# 02_4G.net
KiCad netlist of a schematic drawn in Altium Designer
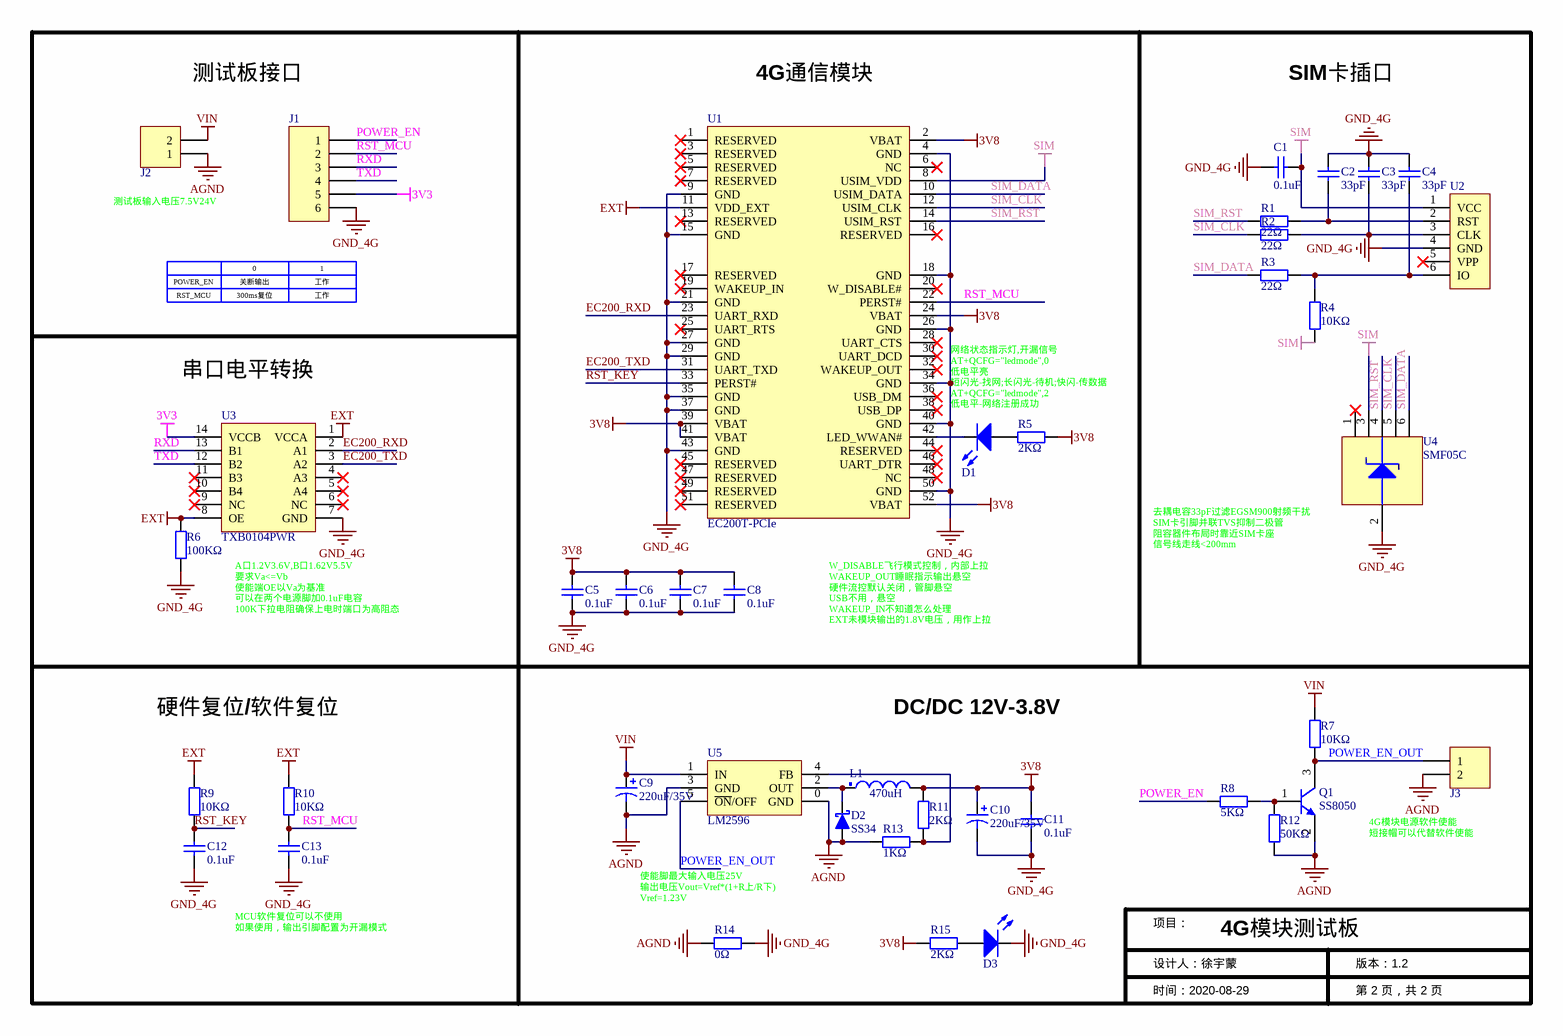
[diagram p0: 02_4G模块测试板原理图.SchDoc]

(export (version "E")
  (design (tool "Eeschema 10.0.6"))
  (components
    (comp (ref "C1")
      (value "0.1uF")
      (footprint "CAP-0603")
      (description "无极性电容")
      (fields (field (name "Comment") "Cap") (field (name "PUBLISHER") "Altium Limited"))
      (libsource (lib "Arrowy_Racing") (part "Cap"))
    )
    (comp (ref "C2")
      (value "33pF")
      (footprint "CAP-0603")
      (description "无极性电容")
      (fields (field (name "Comment") "Cap") (field (name "PUBLISHER") "Altium Limited"))
      (libsource (lib "Arrowy_Racing") (part "Cap"))
    )
    (comp (ref "C3")
      (value "33pF")
      (footprint "CAP-0603")
      (description "无极性电容")
      (fields (field (name "Comment") "Cap") (field (name "PUBLISHER") "Altium Limited"))
      (libsource (lib "Arrowy_Racing") (part "Cap"))
    )
    (comp (ref "C4")
      (value "33pF")
      (footprint "CAP-0603")
      (description "无极性电容")
      (fields (field (name "Comment") "Cap") (field (name "PUBLISHER") "Altium Limited"))
      (libsource (lib "Arrowy_Racing") (part "Cap"))
    )
    (comp (ref "C5")
      (value "0.1uF")
      (footprint "CAP-0603")
      (description "无极性电容")
      (fields (field (name "Comment") "Cap") (field (name "PUBLISHER") "Altium Limited"))
      (libsource (lib "Arrowy_Racing") (part "Cap"))
    )
    (comp (ref "C6")
      (value "0.1uF")
      (footprint "CAP-0603")
      (description "无极性电容")
      (fields (field (name "Comment") "Cap") (field (name "PUBLISHER") "Altium Limited"))
      (libsource (lib "Arrowy_Racing") (part "Cap"))
    )
    (comp (ref "C7")
      (value "0.1uF")
      (footprint "CAP-0603")
      (description "无极性电容")
      (fields (field (name "Comment") "Cap") (field (name "PUBLISHER") "Altium Limited"))
      (libsource (lib "Arrowy_Racing") (part "Cap"))
    )
    (comp (ref "C8")
      (value "0.1uF")
      (footprint "CAP-0603")
      (description "无极性电容")
      (fields (field (name "Comment") "Cap") (field (name "PUBLISHER") "Altium Limited"))
      (libsource (lib "Arrowy_Racing") (part "Cap"))
    )
    (comp (ref "C9")
      (value "220uF/35V")
      (footprint "Cap8x10.5mm")
      (description "贴片电解电容 8*10.5mm")
      (fields (field (name "Comment") "Cap Pol") (field (name "PUBLISHER") "Altium Limited"))
      (libsource (lib "元件库") (part "Cap Pol"))
    )
    (comp (ref "C10")
      (value "220uF/35V")
      (footprint "Cap8x10.5mm")
      (description "贴片电解电容 8*10.5mm")
      (fields (field (name "Comment") "Cap Pol") (field (name "PUBLISHER") "Altium Limited"))
      (libsource (lib "元件库") (part "Cap Pol"))
    )
    (comp (ref "C11")
      (value "0.1uF")
      (footprint "CAP-0603")
      (description "无极性电容")
      (fields (field (name "Comment") "Cap") (field (name "PUBLISHER") "Altium Limited"))
      (libsource (lib "Arrowy_Racing") (part "Cap"))
    )
    (comp (ref "C12")
      (value "0.1uF")
      (footprint "CAP-0603")
      (description "无极性电容")
      (fields (field (name "Comment") "Cap") (field (name "PUBLISHER") "Altium Limited"))
      (libsource (lib "Arrowy_Racing") (part "Cap"))
    )
    (comp (ref "C13")
      (value "0.1uF")
      (footprint "CAP-0603")
      (description "无极性电容")
      (fields (field (name "Comment") "Cap") (field (name "PUBLISHER") "Altium Limited"))
      (libsource (lib "Arrowy_Racing") (part "Cap"))
    )
    (comp (ref "D1")
      (value "LED")
      (footprint "LED_0805")
      (description "发光二极管")
      (fields (field (name "PUBLISHER") "Altium Limited"))
      (libsource (lib "Arrowy_Racing") (part "LED"))
    )
    (comp (ref "D2")
      (value "SS34")
      (footprint "SMA(DO-214AC)")
      (description "Schottky Diode")
      (fields (field (name "PUBLISHER") "Altium Limited"))
      (libsource (lib "元件库") (part "D Schottky"))
    )
    (comp (ref "D3")
      (value "LED")
      (footprint "LED_0805")
      (description "发光二极管")
      (fields (field (name "PUBLISHER") "Altium Limited"))
      (libsource (lib "Arrowy_Racing") (part "LED"))
    )
    (comp (ref "J1")
      (value "Header6")
      (footprint "Header_6x1_2.54_排针")
      (description "接插件")
      (libsource (lib "Arrowy_Racing") (part "Header6"))
    )
    (comp (ref "J2")
      (value "Header 2")
      (footprint "Header_HT_2P_5.08_Right")
      (description "接插件")
      (fields (field (name "PUBLISHER") "Altium Limited"))
      (libsource (lib "Arrowy_Racing") (part "Header 2"))
    )
    (comp (ref "J3")
      (value "Header 2")
      (footprint "Header_2X1_2.54")
      (description "接插件")
      (fields (field (name "PUBLISHER") "Altium Limited"))
      (libsource (lib "") (part "Header 2_1"))
    )
    (comp (ref "L1")
      (value "470uH")
      (footprint "CD43")
      (description "贴片功率电感")
      (fields (field (name "Comment") "Inductor") (field (name "PUBLISHER") "Altium Limited"))
      (libsource (lib "元件库") (part "Inductor"))
    )
    (comp (ref "Q1")
      (value "SS8050")
      (footprint "SOT-23")
      (description "NPN贴片三极管")
      (fields (field (name "PUBLISHER") "Altium Limited"))
      (libsource (lib "Arrowy_Racing") (part "SS8050"))
    )
    (comp (ref "R1")
      (value "22Ω")
      (footprint "0603")
      (description "贴片电阻")
      (fields (field (name "Comment") "Res") (field (name "PUBLISHER") "Altium Limited"))
      (libsource (lib "Arrowy_Racing") (part "Res"))
    )
    (comp (ref "R2")
      (value "22Ω")
      (footprint "0603")
      (description "贴片电阻")
      (fields (field (name "Comment") "Res") (field (name "PUBLISHER") "Altium Limited"))
      (libsource (lib "Arrowy_Racing") (part "Res"))
    )
    (comp (ref "R3")
      (value "22Ω")
      (footprint "0603")
      (description "贴片电阻")
      (fields (field (name "Comment") "Res") (field (name "PUBLISHER") "Altium Limited"))
      (libsource (lib "Arrowy_Racing") (part "Res"))
    )
    (comp (ref "R4")
      (value "10KΩ")
      (footprint "0603")
      (description "贴片电阻")
      (fields (field (name "Comment") "Res") (field (name "PUBLISHER") "Altium Limited"))
      (libsource (lib "") (part "Res_2"))
    )
    (comp (ref "R5")
      (value "2KΩ")
      (footprint "0603")
      (description "贴片电阻")
      (fields (field (name "Comment") "Res") (field (name "PUBLISHER") "Altium Limited"))
      (libsource (lib "") (part "Res_1"))
    )
    (comp (ref "R6")
      (value "100KΩ")
      (footprint "0603")
      (description "贴片电阻")
      (fields (field (name "Comment") "Res") (field (name "PUBLISHER") "Altium Limited"))
      (libsource (lib "Arrowy_Racing") (part "Res"))
    )
    (comp (ref "R7")
      (value "10KΩ")
      (footprint "0603")
      (description "贴片电阻")
      (fields (field (name "Comment") "Res") (field (name "PUBLISHER") "Altium Limited"))
      (libsource (lib "") (part "Res_2"))
    )
    (comp (ref "R8")
      (value "5KΩ")
      (footprint "0603")
      (description "贴片电阻")
      (fields (field (name "Comment") "Res") (field (name "PUBLISHER") "Altium Limited"))
      (libsource (lib "Arrowy_Racing") (part "Res"))
    )
    (comp (ref "R9")
      (value "10KΩ")
      (footprint "0603")
      (description "贴片电阻")
      (fields (field (name "Comment") "Res") (field (name "PUBLISHER") "Altium Limited"))
      (libsource (lib "") (part "Res_3"))
    )
    (comp (ref "R10")
      (value "10KΩ")
      (footprint "0603")
      (description "贴片电阻")
      (fields (field (name "Comment") "Res") (field (name "PUBLISHER") "Altium Limited"))
      (libsource (lib "") (part "Res_2"))
    )
    (comp (ref "R11")
      (value "2KΩ")
      (footprint "0603")
      (description "贴片电阻")
      (fields (field (name "Comment") "Res") (field (name "PUBLISHER") "Altium Limited"))
      (libsource (lib "") (part "Res_2"))
    )
    (comp (ref "R12")
      (value "50KΩ")
      (footprint "0603")
      (description "贴片电阻")
      (fields (field (name "Comment") "Res") (field (name "PUBLISHER") "Altium Limited"))
      (libsource (lib "") (part "Res_2"))
    )
    (comp (ref "R13")
      (value "1KΩ")
      (footprint "0603")
      (description "贴片电阻")
      (fields (field (name "Comment") "Res") (field (name "PUBLISHER") "Altium Limited"))
      (libsource (lib "Arrowy_Racing") (part "Res"))
    )
    (comp (ref "R14")
      (value "0Ω")
      (footprint "0805")
      (description "贴片电阻")
      (fields (field (name "Comment") "Res") (field (name "PUBLISHER") "Altium Limited"))
      (libsource (lib "Arrowy_Racing") (part "Res"))
    )
    (comp (ref "R15")
      (value "2KΩ")
      (footprint "0603")
      (description "贴片电阻")
      (fields (field (name "Comment") "Res") (field (name "PUBLISHER") "Altium Limited"))
      (libsource (lib "") (part "Res_1"))
    )
    (comp (ref "U1")
      (value "EC200T-PCIe")
      (footprint "miniPCIe1")
      (libsource (lib "Arrowy_Racing") (part "EC200T-PCIe"))
    )
    (comp (ref "U2")
      (value "nano_sim")
      (footprint "Nano_SIM_6P")
      (libsource (lib "Arrowy_Racing") (part "nano_sim"))
    )
    (comp (ref "U3")
      (value "TXB0104PWR")
      (footprint "TSSOP-14")
      (description "电平转换芯片")
      (libsource (lib "Arrowy_Racing") (part "TXB0104PWR"))
    )
    (comp (ref "U4") (value "SMF05C") (footprint "SOT-363") (libsource (lib "Arrowy_Racing") (part "SMF05C")))
    (comp (ref "U5")
      (value "LM2596")
      (footprint "TO-263-5 无背面散热")
      (description "DC/DC")
      (libsource (lib "Arrowy_Racing") (part "LM2596"))
    )
  )
  (nets
    (net (code "1") (name "/EC200_RXD") (class "Default")
      (node (ref "U1") (pin "23") (pinfunction "UART_RXD_23") (pintype "passive"))
      (node (ref "U3") (pin "2") (pinfunction "A1_2") (pintype "passive"))
    )
    (net (code "2") (name "/EC200_TXD") (class "Default")
      (node (ref "U1") (pin "31") (pinfunction "UART_TXD_31") (pintype "passive"))
      (node (ref "U3") (pin "3") (pinfunction "A2_3") (pintype "passive"))
    )
    (net (code "3") (name "/POWER_EN") (class "Default")
      (node (ref "J1") (pin "1") (pinfunction "1_1") (pintype "passive"))
      (node (ref "R8") (pin "1") (pinfunction "1_1") (pintype "passive"))
    )
    (net (code "4") (name "/POWER_EN_OUT") (class "Default")
      (node (ref "J3") (pin "1") (pinfunction "1_1") (pintype "passive"))
      (node (ref "Q1") (pin "3") (pinfunction "C_3") (pintype "passive"))
      (node (ref "R7") (pin "2") (pinfunction "2_2") (pintype "passive"))
      (node (ref "U5") (pin "5") (pinfunction "~{ON}/OFF_5") (pintype "passive"))
    )
    (net (code "5") (name "/RST_KEY") (class "Default")
      (node (ref "C12") (pin "2") (pinfunction "2_2") (pintype "passive"))
      (node (ref "R9") (pin "1") (pinfunction "1_1") (pintype "passive"))
      (node (ref "U1") (pin "33") (pinfunction "PERST#_33") (pintype "passive"))
    )
    (net (code "6") (name "/RST_MCU") (class "Default")
      (node (ref "C13") (pin "1") (pinfunction "1_1") (pintype "passive"))
      (node (ref "J1") (pin "2") (pinfunction "2_2") (pintype "passive"))
      (node (ref "R10") (pin "2") (pinfunction "2_2") (pintype "passive"))
      (node (ref "U1") (pin "22") (pinfunction "PERST#_22") (pintype "passive"))
    )
    (net (code "7") (name "/RXD") (class "Default")
      (node (ref "J1") (pin "3") (pinfunction "3_3") (pintype "passive"))
      (node (ref "U3") (pin "13") (pinfunction "B1_13") (pintype "passive"))
    )
    (net (code "8") (name "/SIM_CLK") (class "Default")
      (node (ref "R2") (pin "1") (pinfunction "1_1") (pintype "passive"))
      (node (ref "U1") (pin "12") (pinfunction "USIM_CLK_12") (pintype "passive"))
      (node (ref "U4") (pin "5") (pinfunction "gnd_5") (pintype "passive"))
    )
    (net (code "9") (name "/SIM_DATA") (class "Default")
      (node (ref "R3") (pin "1") (pinfunction "1_1") (pintype "passive"))
      (node (ref "U1") (pin "10") (pinfunction "USIM_DATA_10") (pintype "passive"))
      (node (ref "U4") (pin "6") (pinfunction "gnd_6") (pintype "passive"))
    )
    (net (code "10") (name "/SIM_RST") (class "Default")
      (node (ref "R1") (pin "1") (pinfunction "1_1") (pintype "passive"))
      (node (ref "U1") (pin "14") (pinfunction "USIM_RST_14") (pintype "passive"))
      (node (ref "U4") (pin "4") (pinfunction "gnd_4") (pintype "passive"))
    )
    (net (code "11") (name "/TXD") (class "Default")
      (node (ref "J1") (pin "4") (pinfunction "4_4") (pintype "passive"))
      (node (ref "U3") (pin "12") (pinfunction "B2_12") (pintype "passive"))
    )
    (net (code "12") (name "3V3") (class "Default")
      (node (ref "J1") (pin "5") (pinfunction "5_5") (pintype "passive"))
      (node (ref "U3") (pin "14") (pinfunction "VCCB_14") (pintype "passive"))
    )
    (net (code "13") (name "3V8") (class "Default")
      (node (ref "C10") (pin "1") (pinfunction "1_1") (pintype "passive"))
      (node (ref "C11") (pin "2") (pinfunction "2_2") (pintype "passive"))
      (node (ref "C5") (pin "2") (pinfunction "2_2") (pintype "passive"))
      (node (ref "C6") (pin "2") (pinfunction "2_2") (pintype "passive"))
      (node (ref "C7") (pin "2") (pinfunction "2_2") (pintype "passive"))
      (node (ref "C8") (pin "2") (pinfunction "2_2") (pintype "passive"))
      (node (ref "L1") (pin "2") (pinfunction "2_2") (pintype "passive"))
      (node (ref "R11") (pin "1") (pinfunction "1_1") (pintype "passive"))
      (node (ref "R15") (pin "2") (pinfunction "2_2") (pintype "passive"))
      (node (ref "R5") (pin "1") (pinfunction "1_1") (pintype "passive"))
      (node (ref "U1") (pin "2") (pinfunction "VBAT_2") (pintype "passive"))
      (node (ref "U1") (pin "24") (pinfunction "VBAT_24") (pintype "passive"))
      (node (ref "U1") (pin "39") (pinfunction "VBAT_39") (pintype "passive"))
      (node (ref "U1") (pin "41") (pinfunction "VBAT_41") (pintype "passive"))
      (node (ref "U1") (pin "52") (pinfunction "VBAT_52") (pintype "passive"))
    )
    (net (code "14") (name "AGND") (class "Default")
      (node (ref "C9") (pin "2") (pinfunction "2_2") (pintype "passive"))
      (node (ref "D2") (pin "1") (pinfunction "A_1") (pintype "passive"))
      (node (ref "J2") (pin "1") (pinfunction "1_1") (pintype "passive"))
      (node (ref "J3") (pin "2") (pinfunction "2_2") (pintype "passive"))
      (node (ref "Q1") (pin "2") (pinfunction "E_2") (pintype "passive"))
      (node (ref "R12") (pin "2") (pinfunction "2_2") (pintype "passive"))
      (node (ref "R13") (pin "1") (pinfunction "1_1") (pintype "passive"))
      (node (ref "R14") (pin "1") (pinfunction "1_1") (pintype "passive"))
      (node (ref "U5") (pin "0") (pinfunction "GND_0") (pintype "passive"))
      (node (ref "U5") (pin "3") (pinfunction "GND_3") (pintype "passive"))
    )
    (net (code "15") (name "EXT") (class "Default")
      (node (ref "R10") (pin "1") (pinfunction "1_1") (pintype "passive"))
      (node (ref "R6") (pin "2") (pinfunction "2_2") (pintype "passive"))
      (node (ref "R9") (pin "2") (pinfunction "2_2") (pintype "passive"))
      (node (ref "U1") (pin "11") (pinfunction "VDD_EXT_11") (pintype "passive"))
      (node (ref "U3") (pin "1") (pinfunction "VCCA_1") (pintype "passive"))
      (node (ref "U3") (pin "8") (pinfunction "OE_8") (pintype "passive"))
    )
    (net (code "16") (name "GND_4G") (class "Default")
      (node (ref "C1") (pin "2") (pinfunction "2_2") (pintype "passive"))
      (node (ref "C10") (pin "2") (pinfunction "2_2") (pintype "passive"))
      (node (ref "C11") (pin "1") (pinfunction "1_1") (pintype "passive"))
      (node (ref "C12") (pin "1") (pinfunction "1_1") (pintype "passive"))
      (node (ref "C13") (pin "2") (pinfunction "2_2") (pintype "passive"))
      (node (ref "C2") (pin "1") (pinfunction "1_1") (pintype "passive"))
      (node (ref "C3") (pin "1") (pinfunction "1_1") (pintype "passive"))
      (node (ref "C4") (pin "2") (pinfunction "2_2") (pintype "passive"))
      (node (ref "C5") (pin "1") (pinfunction "1_1") (pintype "passive"))
      (node (ref "C6") (pin "1") (pinfunction "1_1") (pintype "passive"))
      (node (ref "C7") (pin "1") (pinfunction "1_1") (pintype "passive"))
      (node (ref "C8") (pin "1") (pinfunction "1_1") (pintype "passive"))
      (node (ref "D3") (pin "2") (pinfunction "K_2") (pintype "passive"))
      (node (ref "J1") (pin "6") (pinfunction "6_6") (pintype "passive"))
      (node (ref "R14") (pin "2") (pinfunction "2_2") (pintype "passive"))
      (node (ref "R6") (pin "1") (pinfunction "1_1") (pintype "passive"))
      (node (ref "U1") (pin "15") (pinfunction "GND_15") (pintype "passive"))
      (node (ref "U1") (pin "18") (pinfunction "GND_18") (pintype "passive"))
      (node (ref "U1") (pin "21") (pinfunction "GND_21") (pintype "passive"))
      (node (ref "U1") (pin "26") (pinfunction "GND_26") (pintype "passive"))
      (node (ref "U1") (pin "27") (pinfunction "GND_27") (pintype "passive"))
      (node (ref "U1") (pin "29") (pinfunction "GND_29") (pintype "passive"))
      (node (ref "U1") (pin "34") (pinfunction "GND_34") (pintype "passive"))
      (node (ref "U1") (pin "35") (pinfunction "GND_35") (pintype "passive"))
      (node (ref "U1") (pin "37") (pinfunction "GND_37") (pintype "passive"))
      (node (ref "U1") (pin "4") (pinfunction "GND_4") (pintype "passive"))
      (node (ref "U1") (pin "40") (pinfunction "GND_40") (pintype "passive"))
      (node (ref "U1") (pin "43") (pinfunction "GND_43") (pintype "passive"))
      (node (ref "U1") (pin "50") (pinfunction "GND_50") (pintype "passive"))
      (node (ref "U1") (pin "9") (pinfunction "GND_9") (pintype "passive"))
      (node (ref "U2") (pin "4") (pinfunction "GND_4") (pintype "passive"))
      (node (ref "U3") (pin "7") (pinfunction "GND_7") (pintype "passive"))
      (node (ref "U4") (pin "2") (pinfunction "gnd_2") (pintype "passive"))
    )
    (net (code "17") (name "Net-(D1-A)") (class "Default")
      (node (ref "D1") (pin "1") (pinfunction "A_1") (pintype "passive"))
      (node (ref "R5") (pin "2") (pinfunction "2_2") (pintype "passive"))
    )
    (net (code "18") (name "Net-(D1-K)") (class "Default")
      (node (ref "D1") (pin "2") (pinfunction "K_2") (pintype "passive"))
      (node (ref "U1") (pin "42") (pinfunction "LED_WWAN#_42") (pintype "passive"))
    )
    (net (code "19") (name "Net-(D2-K)") (class "Default")
      (node (ref "D2") (pin "2") (pinfunction "K_2") (pintype "passive"))
      (node (ref "L1") (pin "1") (pinfunction "1_1") (pintype "passive"))
      (node (ref "U5") (pin "2") (pinfunction "OUT_2") (pintype "passive"))
    )
    (net (code "20") (name "Net-(D3-A)") (class "Default")
      (node (ref "D3") (pin "1") (pinfunction "A_1") (pintype "passive"))
      (node (ref "R15") (pin "1") (pinfunction "1_1") (pintype "passive"))
    )
    (net (code "21") (name "Net-(Q1-B)") (class "Default")
      (node (ref "Q1") (pin "1") (pinfunction "B_1") (pintype "passive"))
      (node (ref "R12") (pin "1") (pinfunction "1_1") (pintype "passive"))
      (node (ref "R8") (pin "2") (pinfunction "2_2") (pintype "passive"))
    )
    (net (code "22") (name "Net-(U2-CLK)") (class "Default")
      (node (ref "C3") (pin "2") (pinfunction "2_2") (pintype "passive"))
      (node (ref "R2") (pin "2") (pinfunction "2_2") (pintype "passive"))
      (node (ref "U2") (pin "3") (pinfunction "CLK_3") (pintype "passive"))
    )
    (net (code "23") (name "Net-(U2-IO)") (class "Default")
      (node (ref "C4") (pin "1") (pinfunction "1_1") (pintype "passive"))
      (node (ref "R3") (pin "2") (pinfunction "2_2") (pintype "passive"))
      (node (ref "R4") (pin "1") (pinfunction "1_1") (pintype "passive"))
      (node (ref "U2") (pin "6") (pinfunction "IO_6") (pintype "passive"))
    )
    (net (code "24") (name "Net-(U2-RST)") (class "Default")
      (node (ref "C2") (pin "2") (pinfunction "2_2") (pintype "passive"))
      (node (ref "R1") (pin "2") (pinfunction "2_2") (pintype "passive"))
      (node (ref "U2") (pin "2") (pinfunction "RST_2") (pintype "passive"))
    )
    (net (code "25") (name "Net-(U5-FB)") (class "Default")
      (node (ref "R11") (pin "2") (pinfunction "2_2") (pintype "passive"))
      (node (ref "R13") (pin "2") (pinfunction "2_2") (pintype "passive"))
      (node (ref "U5") (pin "4") (pinfunction "FB_4") (pintype "passive"))
    )
    (net (code "26") (name "SIM") (class "Default")
      (node (ref "C1") (pin "1") (pinfunction "1_1") (pintype "passive"))
      (node (ref "R4") (pin "2") (pinfunction "2_2") (pintype "passive"))
      (node (ref "U1") (pin "8") (pinfunction "USIM_VDD_8") (pintype "passive"))
      (node (ref "U2") (pin "1") (pinfunction "VCC_1") (pintype "passive"))
      (node (ref "U4") (pin "3") (pinfunction "gnd_3") (pintype "passive"))
    )
    (net (code "27") (name "VIN") (class "Default")
      (node (ref "C9") (pin "1") (pinfunction "1_1") (pintype "passive"))
      (node (ref "J2") (pin "2") (pinfunction "2_2") (pintype "passive"))
      (node (ref "R7") (pin "1") (pinfunction "1_1") (pintype "passive"))
      (node (ref "U5") (pin "1") (pinfunction "IN_1") (pintype "passive"))
    )
    (net (code "28") (name "unconnected-(U1-NC-Pad6)") (class "Default")
      (node (ref "U1") (pin "6") (pinfunction "NC_6") (pintype "passive+no_connect"))
    )
    (net (code "29") (name "unconnected-(U1-NC-Pad48)") (class "Default")
      (node (ref "U1") (pin "48") (pinfunction "NC_48") (pintype "passive+no_connect"))
    )
    (net (code "30") (name "unconnected-(U1-RESERVED-Pad1)") (class "Default")
      (node (ref "U1") (pin "1") (pinfunction "RESERVED_1") (pintype "passive+no_connect"))
    )
    (net (code "31") (name "unconnected-(U1-RESERVED-Pad3)") (class "Default")
      (node (ref "U1") (pin "3") (pinfunction "RESERVED_3") (pintype "passive+no_connect"))
    )
    (net (code "32") (name "unconnected-(U1-RESERVED-Pad5)") (class "Default")
      (node (ref "U1") (pin "5") (pinfunction "RESERVED_5") (pintype "passive+no_connect"))
    )
    (net (code "33") (name "unconnected-(U1-RESERVED-Pad7)") (class "Default")
      (node (ref "U1") (pin "7") (pinfunction "RESERVED_7") (pintype "passive+no_connect"))
    )
    (net (code "34") (name "unconnected-(U1-RESERVED-Pad13)") (class "Default")
      (node (ref "U1") (pin "13") (pinfunction "RESERVED_13") (pintype "passive+no_connect"))
    )
    (net (code "35") (name "unconnected-(U1-RESERVED-Pad16)") (class "Default")
      (node (ref "U1") (pin "16") (pinfunction "RESERVED_16") (pintype "passive+no_connect"))
    )
    (net (code "36") (name "unconnected-(U1-RESERVED-Pad17)") (class "Default")
      (node (ref "U1") (pin "17") (pinfunction "RESERVED_17") (pintype "passive+no_connect"))
    )
    (net (code "37") (name "unconnected-(U1-RESERVED-Pad44)") (class "Default")
      (node (ref "U1") (pin "44") (pinfunction "RESERVED_44") (pintype "passive+no_connect"))
    )
    (net (code "38") (name "unconnected-(U1-RESERVED-Pad45)") (class "Default")
      (node (ref "U1") (pin "45") (pinfunction "RESERVED_45") (pintype "passive+no_connect"))
    )
    (net (code "39") (name "unconnected-(U1-RESERVED-Pad47)") (class "Default")
      (node (ref "U1") (pin "47") (pinfunction "RESERVED_47") (pintype "passive+no_connect"))
    )
    (net (code "40") (name "unconnected-(U1-RESERVED-Pad49)") (class "Default")
      (node (ref "U1") (pin "49") (pinfunction "RESERVED_49") (pintype "passive+no_connect"))
    )
    (net (code "41") (name "unconnected-(U1-RESERVED-Pad51)") (class "Default")
      (node (ref "U1") (pin "51") (pinfunction "RESERVED_51") (pintype "passive+no_connect"))
    )
    (net (code "42") (name "unconnected-(U1-UART_CTS-Pad28)") (class "Default")
      (node (ref "U1") (pin "28") (pinfunction "UART_CTS_28") (pintype "passive+no_connect"))
    )
    (net (code "43") (name "unconnected-(U1-UART_DCD-Pad30)") (class "Default")
      (node (ref "U1") (pin "30") (pinfunction "UART_DCD_30") (pintype "passive+no_connect"))
    )
    (net (code "44") (name "unconnected-(U1-UART_DTR-Pad46)") (class "Default")
      (node (ref "U1") (pin "46") (pinfunction "UART_DTR_46") (pintype "passive+no_connect"))
    )
    (net (code "45") (name "unconnected-(U1-UART_RTS-Pad25)") (class "Default")
      (node (ref "U1") (pin "25") (pinfunction "UART_RTS_25") (pintype "passive+no_connect"))
    )
    (net (code "46") (name "unconnected-(U1-USB_DM-Pad36)") (class "Default")
      (node (ref "U1") (pin "36") (pinfunction "USB_DM_36") (pintype "passive+no_connect"))
    )
    (net (code "47") (name "unconnected-(U1-USB_DP-Pad38)") (class "Default")
      (node (ref "U1") (pin "38") (pinfunction "USB_DP_38") (pintype "passive+no_connect"))
    )
    (net (code "48") (name "unconnected-(U1-WAKEUP_IN-Pad19)") (class "Default")
      (node (ref "U1") (pin "19") (pinfunction "WAKEUP_IN_19") (pintype "passive+no_connect"))
    )
    (net (code "49") (name "unconnected-(U1-WAKEUP_OUT-Pad32)") (class "Default")
      (node (ref "U1") (pin "32") (pinfunction "WAKEUP_OUT_32") (pintype "passive+no_connect"))
    )
    (net (code "50") (name "unconnected-(U1-W_DISABLE#-Pad20)") (class "Default")
      (node (ref "U1") (pin "20") (pinfunction "W_DISABLE#_20") (pintype "passive+no_connect"))
    )
    (net (code "51") (name "unconnected-(U2-VPP-Pad5)") (class "Default")
      (node (ref "U2") (pin "5") (pinfunction "VPP_5") (pintype "passive+no_connect"))
    )
    (net (code "52") (name "unconnected-(U3-A3-Pad4)") (class "Default")
      (node (ref "U3") (pin "4") (pinfunction "A3_4") (pintype "passive+no_connect"))
    )
    (net (code "53") (name "unconnected-(U3-A4-Pad5)") (class "Default")
      (node (ref "U3") (pin "5") (pinfunction "A4_5") (pintype "passive+no_connect"))
    )
    (net (code "54") (name "unconnected-(U3-B3-Pad11)") (class "Default")
      (node (ref "U3") (pin "11") (pinfunction "B3_11") (pintype "passive+no_connect"))
    )
    (net (code "55") (name "unconnected-(U3-B4-Pad10)") (class "Default")
      (node (ref "U3") (pin "10") (pinfunction "B4_10") (pintype "passive+no_connect"))
    )
    (net (code "56") (name "unconnected-(U3-NC-Pad6)") (class "Default")
      (node (ref "U3") (pin "6") (pinfunction "NC_6") (pintype "passive+no_connect"))
    )
    (net (code "57") (name "unconnected-(U3-NC-Pad9)") (class "Default")
      (node (ref "U3") (pin "9") (pinfunction "NC_9") (pintype "passive+no_connect"))
    )
    (net (code "58") (name "unconnected-(U4-gnd-Pad1)") (class "Default")
      (node (ref "U4") (pin "1") (pinfunction "gnd_1") (pintype "passive+no_connect"))
    )
  )
)
